# LED_board_schematic_pg_2.net
KiCad netlist of a schematic drawn in Altium Designer
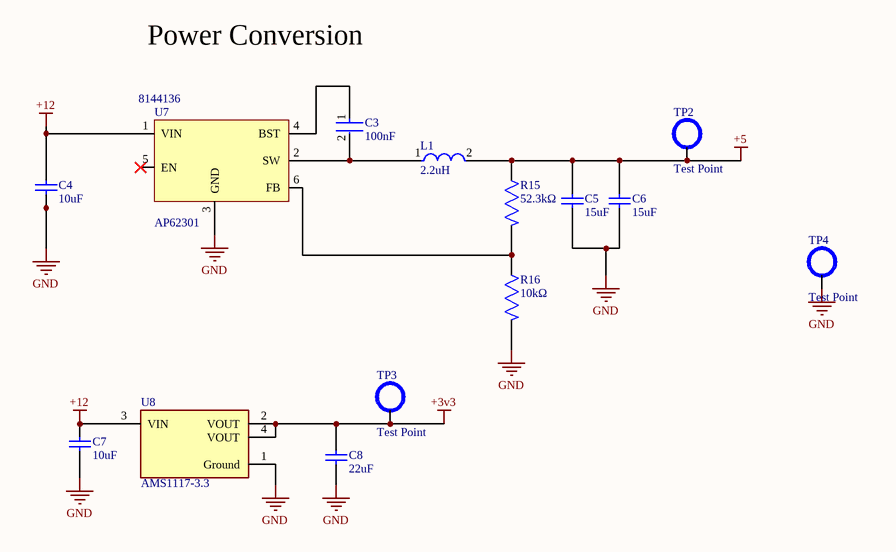
[diagram p0: LED_board_schematic_pg_2.SchDoc]

(export (version "E")
  (design (tool "Eeschema 10.0.6"))
  (components
    (comp (ref "C3")
      (value "100nF")
      (footprint "FP-C0402-BB-MFG")
      (description "CAP CER 0.1UF 10V X5R 0402")
      (fields (field (name "MANUFACTURER") "Kemet") (field (name "TOLERANCE") "0.1"))
      (libsource (lib "Altium Content Vault") (part "b4654b650e69147ec39a6b967a45e02"))
    )
    (comp (ref "C4")
      (value "10uF")
      (footprint "0805 PACKAGE")
      (description "Chip Multilayer Ceramic Capacitors for General Purpose, 0805, 10uF, X5R, 15%, 10%, 16V")
      (libsource (lib "LED_Validation_Sch_Lib") (part "Capacitor"))
    )
    (comp (ref "C5")
      (value "15uF")
      (footprint "0603 PACKAGE")
      (description "Chip Multilayer Ceramic Capacitors for General Purpose, 0603, 15uF, X5R, 15%, 20%, 10V")
      (libsource (lib "LED_Validation_Sch_Lib") (part "Capacitor"))
    )
    (comp (ref "C6")
      (value "15uF")
      (footprint "0603 PACKAGE")
      (description "Chip Multilayer Ceramic Capacitors for General Purpose, 0603, 15uF, X5R, 15%, 20%, 10V")
      (libsource (lib "LED_Validation_Sch_Lib") (part "Capacitor"))
    )
    (comp (ref "C7")
      (value "10uF")
      (footprint "0805 PACKAGE")
      (description "Chip Multilayer Ceramic Capacitors for General Purpose, 0805, 10uF, X5R, 15%, 10%, 16V")
      (libsource (lib "LED_Validation_Sch_Lib") (part "Capacitor"))
    )
    (comp (ref "C8")
      (value "22uF")
      (footprint "0603 PACKAGE")
      (description "Chip Multilayer Ceramic Capacitors for General Purpose, 0603, 22uF, X5R, 15%, 20%, 10V")
      (libsource (lib "LED_Validation_Sch_Lib") (part "Capacitor"))
    )
    (comp (ref "L1")
      (value "2.2uH")
      (footprint "FP-IHLP-1212BZ-11-MFG")
      (description "FIXED IND 2.2UH 3A 46 MOHM SMD")
      (fields (field (name "TOLERANCE") "20%"))
      (libsource (lib "Altium Content Vault") (part "725321dda6339637d4d059423bc1c3c"))
    )
    (comp (ref "R15")
      (value "52.3kΩ")
      (footprint "0402 PACKAGE")
      (description "RES 10K OHM 1% 1/16W 0402")
      (libsource (lib "LED_Validation_Sch_Lib") (part "Resistor"))
    )
    (comp (ref "R16")
      (value "10kΩ")
      (footprint "0402 PACKAGE")
      (description "RES 10K OHM 1% 1/16W 0402")
      (libsource (lib "LED_Validation_Sch_Lib") (part "Resistor"))
    )
    (comp (ref "TP2")
      (value "Test Point")
      (footprint "Test Point")
      (libsource (lib "LED_board") (part "Test Point"))
    )
    (comp (ref "TP3")
      (value "Test Point")
      (footprint "Test Point")
      (libsource (lib "LED_board") (part "Test Point"))
    )
    (comp (ref "TP4")
      (value "Test Point")
      (footprint "Test Point")
      (libsource (lib "LED_board") (part "Test Point"))
    )
    (comp (ref "U7")
      (value "AP62301")
      (footprint "AP62301")
      (description "Buck Converter \r\nSOT-563")
      (fields (field (name "SUPPLIER PART NUMBER 1") "8144136"))
      (libsource (lib "LED_Module_Schematic_Library") (part "AP62301"))
    )
    (comp (ref "U8")
      (value "AMS1117-3.3")
      (footprint "FP-AMS1117-IPC_C")
      (description "LDO Voltage Regulators 1A, 3.3V")
      (fields
        (field (name "OCTOPART") "https://octopart.com/ams1117-3.3-advanced+monolithic+systems-25899300")
        (field (name "MANUFACTURER") "Advanced Monolithic Systems")
      )
      (libsource (lib "Altium Content Vault") (part "8bdbb5f8e77002000e30dd2845d0354"))
    )
  )
  (nets
    (net (code "1") (name "+3v3") (class "Default")
      (node (ref "C8") (pin "2") (pinfunction "2_2") (pintype "passive"))
      (node (ref "TP3") (pin "1") (pinfunction "1_1") (pintype "passive"))
      (node (ref "U8") (pin "2") (pinfunction "VOUT_2") (pintype "passive"))
      (node (ref "U8") (pin "4") (pinfunction "VOUT_4") (pintype "passive"))
    )
    (net (code "2") (name "+5") (class "Default")
      (node (ref "C5") (pin "2") (pinfunction "2_2") (pintype "passive"))
      (node (ref "C6") (pin "2") (pinfunction "2_2") (pintype "passive"))
      (node (ref "L1") (pin "2") (pinfunction "2_2") (pintype "passive"))
      (node (ref "R15") (pin "1") (pinfunction "1_1") (pintype "passive"))
      (node (ref "TP2") (pin "1") (pinfunction "1_1") (pintype "passive"))
    )
    (net (code "3") (name "+12") (class "Default")
      (node (ref "C4") (pin "2") (pinfunction "2_2") (pintype "passive"))
      (node (ref "C7") (pin "2") (pinfunction "2_2") (pintype "passive"))
      (node (ref "U7") (pin "1") (pinfunction "VIN_1") (pintype "passive"))
      (node (ref "U8") (pin "3") (pinfunction "VIN_3") (pintype "power_in"))
    )
    (net (code "4") (name "GND") (class "Default")
      (node (ref "C4") (pin "1") (pinfunction "1_1") (pintype "passive"))
      (node (ref "C5") (pin "1") (pinfunction "1_1") (pintype "passive"))
      (node (ref "C6") (pin "1") (pinfunction "1_1") (pintype "passive"))
      (node (ref "C7") (pin "1") (pinfunction "1_1") (pintype "passive"))
      (node (ref "C8") (pin "1") (pinfunction "1_1") (pintype "passive"))
      (node (ref "R16") (pin "2") (pinfunction "2_2") (pintype "passive"))
      (node (ref "TP4") (pin "1") (pinfunction "1_1") (pintype "passive"))
      (node (ref "U7") (pin "3") (pinfunction "GND_3") (pintype "passive"))
      (node (ref "U8") (pin "1") (pinfunction "Ground_1") (pintype "power_in"))
    )
    (net (code "5") (name "Net-(U7-BST)") (class "Default")
      (node (ref "C3") (pin "1") (pinfunction "1_1") (pintype "passive"))
      (node (ref "U7") (pin "4") (pinfunction "BST_4") (pintype "passive"))
    )
    (net (code "6") (name "Net-(U7-FB)") (class "Default")
      (node (ref "R15") (pin "2") (pinfunction "2_2") (pintype "passive"))
      (node (ref "R16") (pin "1") (pinfunction "1_1") (pintype "passive"))
      (node (ref "U7") (pin "6") (pinfunction "FB_6") (pintype "passive"))
    )
    (net (code "7") (name "Net-(U7-SW)") (class "Default")
      (node (ref "C3") (pin "2") (pinfunction "2_2") (pintype "passive"))
      (node (ref "L1") (pin "1") (pinfunction "1_1") (pintype "passive"))
      (node (ref "U7") (pin "2") (pinfunction "SW_2") (pintype "passive"))
    )
    (net (code "8") (name "unconnected-(U7-EN-Pad5)") (class "Default")
      (node (ref "U7") (pin "5") (pinfunction "EN_5") (pintype "passive+no_connect"))
    )
  )
)
